# logic6_front.net
KiCad netlist of a schematic drawn in Altium Designer
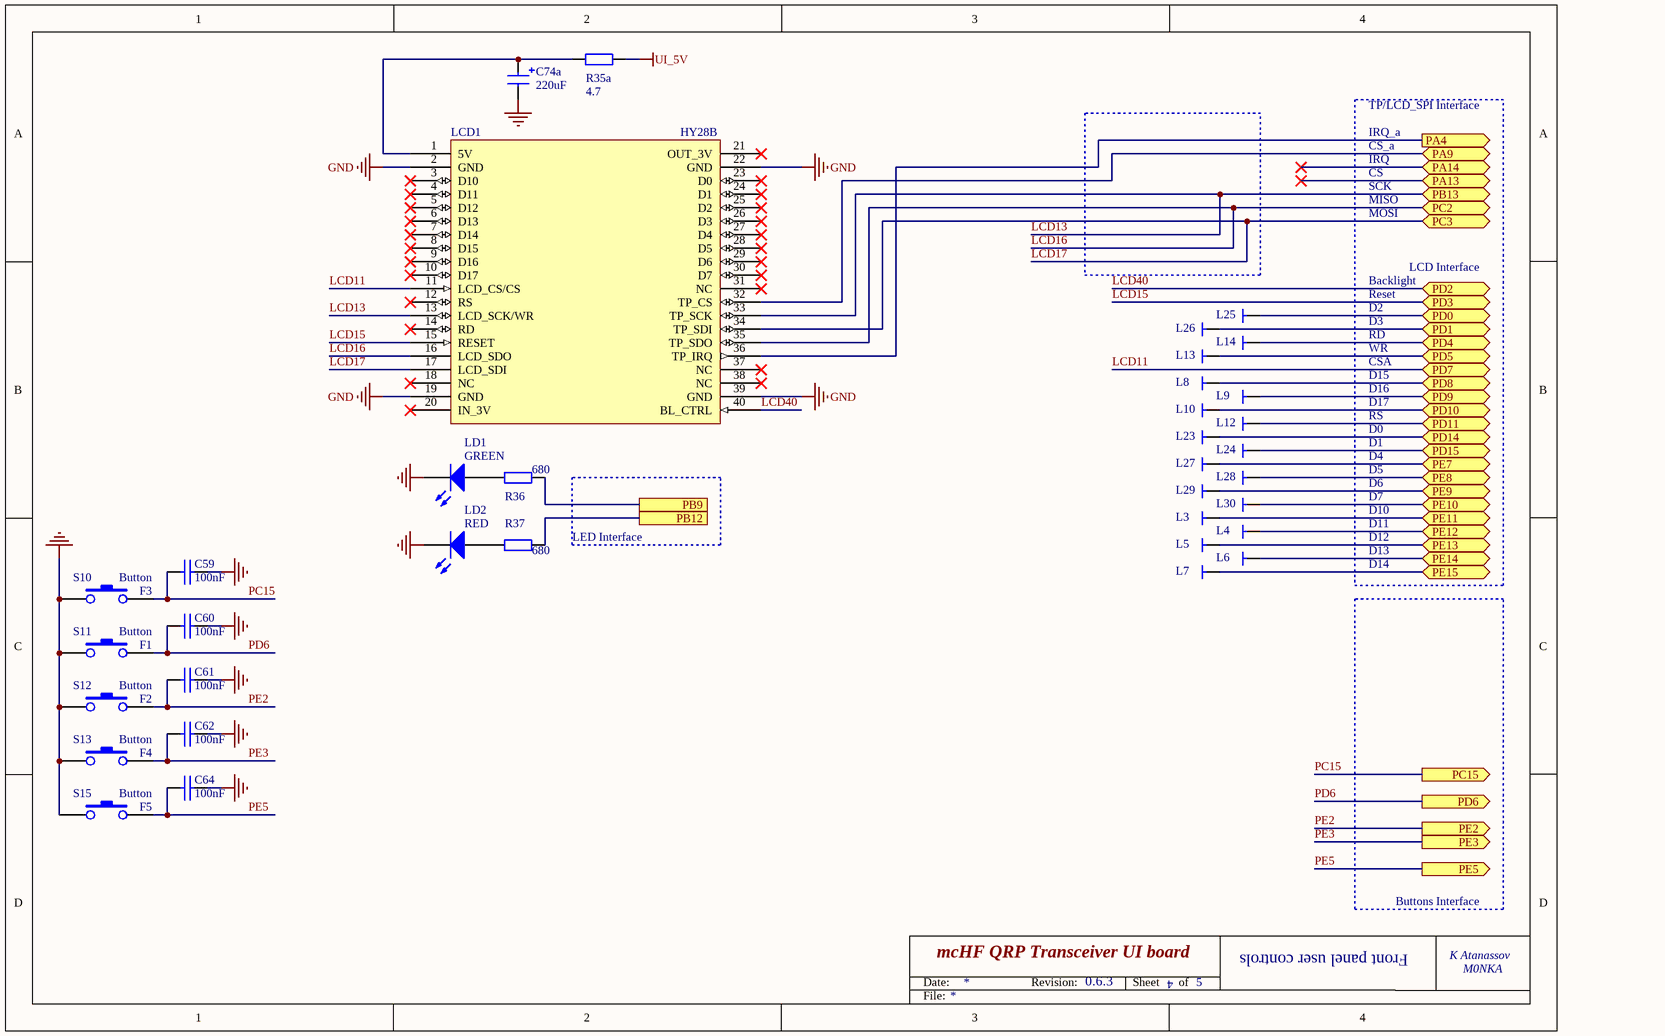
[diagram p0: logic6_front.SchDoc]

(export (version "E")
  (design (tool "Eeschema 10.0.6"))
  (components
    (comp (ref "C59")
      (value "100nF")
      (footprint "0805-Pro")
      (description "Capacitor")
      (libsource (lib "mcHF_ui") (part "CAP"))
    )
    (comp (ref "C60")
      (value "100nF")
      (footprint "0805-Pro")
      (description "Capacitor")
      (libsource (lib "mcHF_ui") (part "CAP"))
    )
    (comp (ref "C61")
      (value "100nF")
      (footprint "0805-Pro")
      (description "Capacitor")
      (libsource (lib "mcHF_ui") (part "CAP"))
    )
    (comp (ref "C62")
      (value "100nF")
      (footprint "0805-Pro")
      (description "Capacitor")
      (libsource (lib "mcHF_ui") (part "CAP"))
    )
    (comp (ref "C64")
      (value "100nF")
      (footprint "0805-Pro")
      (description "Capacitor")
      (libsource (lib "mcHF_ui") (part "CAP"))
    )
    (comp (ref "C74a")
      (value "220uF")
      (footprint "CAP_ALUM")
      (description "Electrolitic capacitor")
      (libsource (lib "mcHF_ui") (part "CAP-POL"))
    )
    (comp (ref "L3")
      (value "TP")
      (footprint "tp")
      (description "Test point")
      (libsource (lib "mcHF_ui_b") (part "TP"))
    )
    (comp (ref "L4")
      (value "TP")
      (footprint "tp")
      (description "Test point")
      (libsource (lib "mcHF_ui_b") (part "TP"))
    )
    (comp (ref "L5")
      (value "TP")
      (footprint "tp")
      (description "Test point")
      (libsource (lib "mcHF_ui_b") (part "TP"))
    )
    (comp (ref "L6")
      (value "TP")
      (footprint "tp")
      (description "Test point")
      (libsource (lib "mcHF_ui_b") (part "TP"))
    )
    (comp (ref "L7")
      (value "TP")
      (footprint "tp")
      (description "Test point")
      (libsource (lib "mcHF_ui_b") (part "TP"))
    )
    (comp (ref "L8")
      (value "TP")
      (footprint "tp")
      (description "Test point")
      (libsource (lib "mcHF_ui_b") (part "TP"))
    )
    (comp (ref "L9")
      (value "TP")
      (footprint "tp")
      (description "Test point")
      (libsource (lib "mcHF_ui_b") (part "TP"))
    )
    (comp (ref "L10")
      (value "TP")
      (footprint "tp")
      (description "Test point")
      (libsource (lib "mcHF_ui_b") (part "TP"))
    )
    (comp (ref "L12")
      (value "TP")
      (footprint "tp")
      (description "Test point")
      (libsource (lib "mcHF_ui_b") (part "TP"))
    )
    (comp (ref "L13")
      (value "TP")
      (footprint "tp")
      (description "Test point")
      (libsource (lib "mcHF_ui_b") (part "TP"))
    )
    (comp (ref "L14")
      (value "TP")
      (footprint "tp")
      (description "Test point")
      (libsource (lib "mcHF_ui_b") (part "TP"))
    )
    (comp (ref "L23")
      (value "TP")
      (footprint "tp")
      (description "Test point")
      (libsource (lib "mcHF_ui_b") (part "TP"))
    )
    (comp (ref "L24")
      (value "TP")
      (footprint "tp")
      (description "Test point")
      (libsource (lib "mcHF_ui_b") (part "TP"))
    )
    (comp (ref "L25")
      (value "TP")
      (footprint "tp")
      (description "Test point")
      (libsource (lib "mcHF_ui_b") (part "TP"))
    )
    (comp (ref "L26")
      (value "TP")
      (footprint "tp")
      (description "Test point")
      (libsource (lib "mcHF_ui_b") (part "TP"))
    )
    (comp (ref "L27")
      (value "TP")
      (footprint "tp")
      (description "Test point")
      (libsource (lib "mcHF_ui_b") (part "TP"))
    )
    (comp (ref "L28")
      (value "TP")
      (footprint "tp")
      (description "Test point")
      (libsource (lib "mcHF_ui_b") (part "TP"))
    )
    (comp (ref "L29")
      (value "TP")
      (footprint "tp")
      (description "Test point")
      (libsource (lib "mcHF_ui_b") (part "TP"))
    )
    (comp (ref "L30")
      (value "TP")
      (footprint "tp")
      (description "Test point")
      (libsource (lib "mcHF_ui_b") (part "TP"))
    )
    (comp (ref "LCD1")
      (value "HY28B")
      (footprint "HY28A")
      (description "2.8 inch TFT LCD")
      (libsource (lib "mcHF_ui") (part "HY28AB"))
    )
    (comp (ref "LD1")
      (value "GREEN")
      (footprint "LED2n")
      (description "LED 3mm")
      (libsource (lib "mcHF_ui") (part "LED2"))
    )
    (comp (ref "LD2")
      (value "RED")
      (footprint "LED2n")
      (description "LED 3mm")
      (libsource (lib "mcHF_ui") (part "LED2"))
    )
    (comp (ref "R35a")
      (value "4.7")
      (footprint "1206")
      (description "Resistor")
      (libsource (lib "mcHF_ui") (part "RES"))
    )
    (comp (ref "R36")
      (value "680")
      (footprint "0805-Pro")
      (description "Resistor")
      (libsource (lib "") (part "RES_1"))
    )
    (comp (ref "R37")
      (value "680")
      (footprint "0805-Pro")
      (description "Resistor")
      (libsource (lib "") (part "RES_1"))
    )
    (comp (ref "S10")
      (value "Button")
      (footprint "BUTTON_SMD2")
      (description "Push Button")
      (fields (field (name "SOFTWARE FUNCTION") "F3"))
      (libsource (lib "mcHF_ui") (part "SW-PB"))
    )
    (comp (ref "S11")
      (value "Button")
      (footprint "BUTTON_SMD2")
      (description "Push Button")
      (fields (field (name "SOFTWARE FUNCTION") "F1"))
      (libsource (lib "mcHF_ui") (part "SW-PB"))
    )
    (comp (ref "S12")
      (value "Button")
      (footprint "BUTTON_SMD2")
      (description "Push Button")
      (fields (field (name "SOFTWARE FUNCTION") "F2"))
      (libsource (lib "mcHF_ui") (part "SW-PB"))
    )
    (comp (ref "S13")
      (value "Button")
      (footprint "BUTTON_SMD2")
      (description "Push Button")
      (fields (field (name "SOFTWARE FUNCTION") "F4"))
      (libsource (lib "mcHF_ui") (part "SW-PB"))
    )
    (comp (ref "S15")
      (value "Button")
      (footprint "BUTTON_SMD2")
      (description "Push Button")
      (fields (field (name "SOFTWARE FUNCTION") "F5"))
      (libsource (lib "mcHF_ui") (part "SW-PB"))
    )
  )
  (nets
    (net (code "1") (name "/LCD11") (class "Default")
      (node (ref "LCD1") (pin "11") (pinfunction "LCD_CS/CS_11") (pintype "input"))
    )
    (net (code "2") (name "/LCD13") (class "Default")
      (node (ref "LCD1") (pin "13") (pinfunction "LCD_SCK/WR_13") (pintype "bidirectional"))
      (node (ref "LCD1") (pin "33") (pinfunction "TP_SCK_33") (pintype "bidirectional"))
    )
    (net (code "3") (name "/LCD15") (class "Default")
      (node (ref "LCD1") (pin "15") (pinfunction "RESET_15") (pintype "input"))
    )
    (net (code "4") (name "/LCD16") (class "Default")
      (node (ref "LCD1") (pin "16") (pinfunction "LCD_SDO_16") (pintype "passive"))
      (node (ref "LCD1") (pin "35") (pinfunction "TP_SDO_35") (pintype "bidirectional"))
    )
    (net (code "5") (name "/LCD17") (class "Default")
      (node (ref "LCD1") (pin "17") (pinfunction "LCD_SDI_17") (pintype "passive"))
      (node (ref "LCD1") (pin "34") (pinfunction "TP_SDI_34") (pintype "bidirectional"))
    )
    (net (code "6") (name "/LCD40") (class "Default")
      (node (ref "LCD1") (pin "40") (pinfunction "BL_CTRL_40") (pintype "input"))
    )
    (net (code "7") (name "/PA4") (class "Default")
      (node (ref "LCD1") (pin "36") (pinfunction "TP_IRQ_36") (pintype "output"))
    )
    (net (code "8") (name "/PA9") (class "Default")
      (node (ref "LCD1") (pin "32") (pinfunction "TP_CS_32") (pintype "bidirectional"))
    )
    (net (code "11") (name "/PB9") (class "Default")
      (node (ref "R36") (pin "2") (pinfunction "2_2") (pintype "passive"))
    )
    (net (code "12") (name "/PB12") (class "Default")
      (node (ref "R37") (pin "2") (pinfunction "2_2") (pintype "passive"))
    )
    (net (code "13") (name "/PC15") (class "Default")
      (node (ref "C59") (pin "2") (pinfunction "2_2") (pintype "passive"))
      (node (ref "S10") (pin "2") (pinfunction "2_2") (pintype "passive"))
    )
    (net (code "14") (name "/PD0") (class "Default")
      (node (ref "L25") (pin "1") (pinfunction "1_1") (pintype "passive"))
    )
    (net (code "15") (name "/PD1") (class "Default")
      (node (ref "L26") (pin "1") (pinfunction "1_1") (pintype "passive"))
    )
    (net (code "16") (name "/PD4") (class "Default")
      (node (ref "L14") (pin "1") (pinfunction "1_1") (pintype "passive"))
    )
    (net (code "17") (name "/PD5") (class "Default")
      (node (ref "L13") (pin "1") (pinfunction "1_1") (pintype "passive"))
    )
    (net (code "18") (name "/PD6") (class "Default")
      (node (ref "C60") (pin "2") (pinfunction "2_2") (pintype "passive"))
      (node (ref "S11") (pin "2") (pinfunction "2_2") (pintype "passive"))
    )
    (net (code "19") (name "/PD8") (class "Default")
      (node (ref "L8") (pin "1") (pinfunction "1_1") (pintype "passive"))
    )
    (net (code "20") (name "/PD9") (class "Default")
      (node (ref "L9") (pin "1") (pinfunction "1_1") (pintype "passive"))
    )
    (net (code "21") (name "/PD10") (class "Default")
      (node (ref "L10") (pin "1") (pinfunction "1_1") (pintype "passive"))
    )
    (net (code "22") (name "/PD11") (class "Default")
      (node (ref "L12") (pin "1") (pinfunction "1_1") (pintype "passive"))
    )
    (net (code "23") (name "/PD14") (class "Default")
      (node (ref "L23") (pin "1") (pinfunction "1_1") (pintype "passive"))
    )
    (net (code "24") (name "/PD15") (class "Default")
      (node (ref "L24") (pin "1") (pinfunction "1_1") (pintype "passive"))
    )
    (net (code "25") (name "/PE2") (class "Default")
      (node (ref "C61") (pin "2") (pinfunction "2_2") (pintype "passive"))
      (node (ref "S12") (pin "2") (pinfunction "2_2") (pintype "passive"))
    )
    (net (code "26") (name "/PE3") (class "Default")
      (node (ref "C62") (pin "2") (pinfunction "2_2") (pintype "passive"))
      (node (ref "S13") (pin "2") (pinfunction "2_2") (pintype "passive"))
    )
    (net (code "27") (name "/PE5") (class "Default")
      (node (ref "C64") (pin "2") (pinfunction "2_2") (pintype "passive"))
      (node (ref "S15") (pin "2") (pinfunction "2_2") (pintype "passive"))
    )
    (net (code "28") (name "/PE7") (class "Default")
      (node (ref "L27") (pin "1") (pinfunction "1_1") (pintype "passive"))
    )
    (net (code "29") (name "/PE8") (class "Default")
      (node (ref "L28") (pin "1") (pinfunction "1_1") (pintype "passive"))
    )
    (net (code "30") (name "/PE9") (class "Default")
      (node (ref "L29") (pin "1") (pinfunction "1_1") (pintype "passive"))
    )
    (net (code "31") (name "/PE10") (class "Default")
      (node (ref "L30") (pin "1") (pinfunction "1_1") (pintype "passive"))
    )
    (net (code "32") (name "/PE11") (class "Default")
      (node (ref "L3") (pin "1") (pinfunction "1_1") (pintype "passive"))
    )
    (net (code "33") (name "/PE12") (class "Default")
      (node (ref "L4") (pin "1") (pinfunction "1_1") (pintype "passive"))
    )
    (net (code "34") (name "/PE13") (class "Default")
      (node (ref "L5") (pin "1") (pinfunction "1_1") (pintype "passive"))
    )
    (net (code "35") (name "/PE14") (class "Default")
      (node (ref "L6") (pin "1") (pinfunction "1_1") (pintype "passive"))
    )
    (net (code "36") (name "/PE15") (class "Default")
      (node (ref "L7") (pin "1") (pinfunction "1_1") (pintype "passive"))
    )
    (net (code "37") (name "GND") (class "Default")
      (node (ref "C59") (pin "1") (pinfunction "1_1") (pintype "passive"))
      (node (ref "C60") (pin "1") (pinfunction "1_1") (pintype "passive"))
      (node (ref "C61") (pin "1") (pinfunction "1_1") (pintype "passive"))
      (node (ref "C62") (pin "1") (pinfunction "1_1") (pintype "passive"))
      (node (ref "C64") (pin "1") (pinfunction "1_1") (pintype "passive"))
      (node (ref "C74a") (pin "2") (pinfunction "2_2") (pintype "passive"))
      (node (ref "LCD1") (pin "19") (pinfunction "GND_19") (pintype "power_in"))
      (node (ref "LCD1") (pin "2") (pinfunction "GND_2") (pintype "power_in"))
      (node (ref "LCD1") (pin "22") (pinfunction "GND_22") (pintype "power_in"))
      (node (ref "LCD1") (pin "39") (pinfunction "GND_39") (pintype "power_in"))
      (node (ref "LD1") (pin "2") (pinfunction "K_2") (pintype "passive"))
      (node (ref "LD2") (pin "2") (pinfunction "K_2") (pintype "passive"))
      (node (ref "S10") (pin "1") (pinfunction "1_1") (pintype "passive"))
      (node (ref "S11") (pin "1") (pinfunction "1_1") (pintype "passive"))
      (node (ref "S12") (pin "1") (pinfunction "1_1") (pintype "passive"))
      (node (ref "S13") (pin "1") (pinfunction "1_1") (pintype "passive"))
      (node (ref "S15") (pin "1") (pinfunction "1_1") (pintype "passive"))
    )
    (net (code "38") (name "Net-(LCD1-5V)") (class "Default")
      (node (ref "C74a") (pin "1") (pinfunction "1_1") (pintype "passive"))
      (node (ref "LCD1") (pin "1") (pinfunction "5V_1") (pintype "power_in"))
      (node (ref "R35a") (pin "2") (pinfunction "2_2") (pintype "passive"))
    )
    (net (code "39") (name "Net-(LD1-A)") (class "Default")
      (node (ref "LD1") (pin "1") (pinfunction "A_1") (pintype "passive"))
      (node (ref "R36") (pin "1") (pinfunction "1_1") (pintype "passive"))
    )
    (net (code "40") (name "Net-(LD2-A)") (class "Default")
      (node (ref "LD2") (pin "1") (pinfunction "A_1") (pintype "passive"))
      (node (ref "R37") (pin "1") (pinfunction "1_1") (pintype "passive"))
    )
    (net (code "41") (name "UI_5V") (class "Default")
      (node (ref "R35a") (pin "1") (pinfunction "1_1") (pintype "passive"))
    )
    (net (code "42") (name "unconnected-(LCD1-D0-Pad23)") (class "Default")
      (node (ref "LCD1") (pin "23") (pinfunction "D0_23") (pintype "bidirectional+no_connect"))
    )
    (net (code "43") (name "unconnected-(LCD1-D1-Pad24)") (class "Default")
      (node (ref "LCD1") (pin "24") (pinfunction "D1_24") (pintype "bidirectional+no_connect"))
    )
    (net (code "44") (name "unconnected-(LCD1-D2-Pad25)") (class "Default")
      (node (ref "LCD1") (pin "25") (pinfunction "D2_25") (pintype "bidirectional+no_connect"))
    )
    (net (code "45") (name "unconnected-(LCD1-D3-Pad26)") (class "Default")
      (node (ref "LCD1") (pin "26") (pinfunction "D3_26") (pintype "bidirectional+no_connect"))
    )
    (net (code "46") (name "unconnected-(LCD1-D4-Pad27)") (class "Default")
      (node (ref "LCD1") (pin "27") (pinfunction "D4_27") (pintype "bidirectional+no_connect"))
    )
    (net (code "47") (name "unconnected-(LCD1-D5-Pad28)") (class "Default")
      (node (ref "LCD1") (pin "28") (pinfunction "D5_28") (pintype "bidirectional+no_connect"))
    )
    (net (code "48") (name "unconnected-(LCD1-D6-Pad29)") (class "Default")
      (node (ref "LCD1") (pin "29") (pinfunction "D6_29") (pintype "bidirectional+no_connect"))
    )
    (net (code "49") (name "unconnected-(LCD1-D7-Pad30)") (class "Default")
      (node (ref "LCD1") (pin "30") (pinfunction "D7_30") (pintype "bidirectional+no_connect"))
    )
    (net (code "50") (name "unconnected-(LCD1-D10-Pad3)") (class "Default")
      (node (ref "LCD1") (pin "3") (pinfunction "D10_3") (pintype "bidirectional+no_connect"))
    )
    (net (code "51") (name "unconnected-(LCD1-D11-Pad4)") (class "Default")
      (node (ref "LCD1") (pin "4") (pinfunction "D11_4") (pintype "bidirectional+no_connect"))
    )
    (net (code "52") (name "unconnected-(LCD1-D12-Pad5)") (class "Default")
      (node (ref "LCD1") (pin "5") (pinfunction "D12_5") (pintype "bidirectional+no_connect"))
    )
    (net (code "53") (name "unconnected-(LCD1-D13-Pad6)") (class "Default")
      (node (ref "LCD1") (pin "6") (pinfunction "D13_6") (pintype "bidirectional+no_connect"))
    )
    (net (code "54") (name "unconnected-(LCD1-D14-Pad7)") (class "Default")
      (node (ref "LCD1") (pin "7") (pinfunction "D14_7") (pintype "bidirectional+no_connect"))
    )
    (net (code "55") (name "unconnected-(LCD1-D15-Pad8)") (class "Default")
      (node (ref "LCD1") (pin "8") (pinfunction "D15_8") (pintype "bidirectional+no_connect"))
    )
    (net (code "56") (name "unconnected-(LCD1-D16-Pad9)") (class "Default")
      (node (ref "LCD1") (pin "9") (pinfunction "D16_9") (pintype "bidirectional+no_connect"))
    )
    (net (code "57") (name "unconnected-(LCD1-D17-Pad10)") (class "Default")
      (node (ref "LCD1") (pin "10") (pinfunction "D17_10") (pintype "bidirectional+no_connect"))
    )
    (net (code "58") (name "unconnected-(LCD1-IN_3V-Pad20)") (class "Default")
      (node (ref "LCD1") (pin "20") (pinfunction "IN_3V_20") (pintype "power_in+no_connect"))
    )
    (net (code "59") (name "unconnected-(LCD1-NC-Pad18)") (class "Default")
      (node (ref "LCD1") (pin "18") (pinfunction "NC_18") (pintype "passive+no_connect"))
    )
    (net (code "60") (name "unconnected-(LCD1-NC-Pad31)") (class "Default")
      (node (ref "LCD1") (pin "31") (pinfunction "NC_31") (pintype "passive+no_connect"))
    )
    (net (code "61") (name "unconnected-(LCD1-NC-Pad37)") (class "Default")
      (node (ref "LCD1") (pin "37") (pinfunction "NC_37") (pintype "passive+no_connect"))
    )
    (net (code "62") (name "unconnected-(LCD1-NC-Pad38)") (class "Default")
      (node (ref "LCD1") (pin "38") (pinfunction "NC_38") (pintype "passive+no_connect"))
    )
    (net (code "63") (name "unconnected-(LCD1-OUT_3V-Pad21)") (class "Default")
      (node (ref "LCD1") (pin "21") (pinfunction "OUT_3V_21") (pintype "power_in+no_connect"))
    )
    (net (code "64") (name "unconnected-(LCD1-RD-Pad14)") (class "Default")
      (node (ref "LCD1") (pin "14") (pinfunction "RD_14") (pintype "bidirectional+no_connect"))
    )
    (net (code "65") (name "unconnected-(LCD1-RS-Pad12)") (class "Default")
      (node (ref "LCD1") (pin "12") (pinfunction "RS_12") (pintype "bidirectional+no_connect"))
    )
  )
)
